# Sens_BMP085.net
KiCad netlist of a schematic drawn in EAGLE
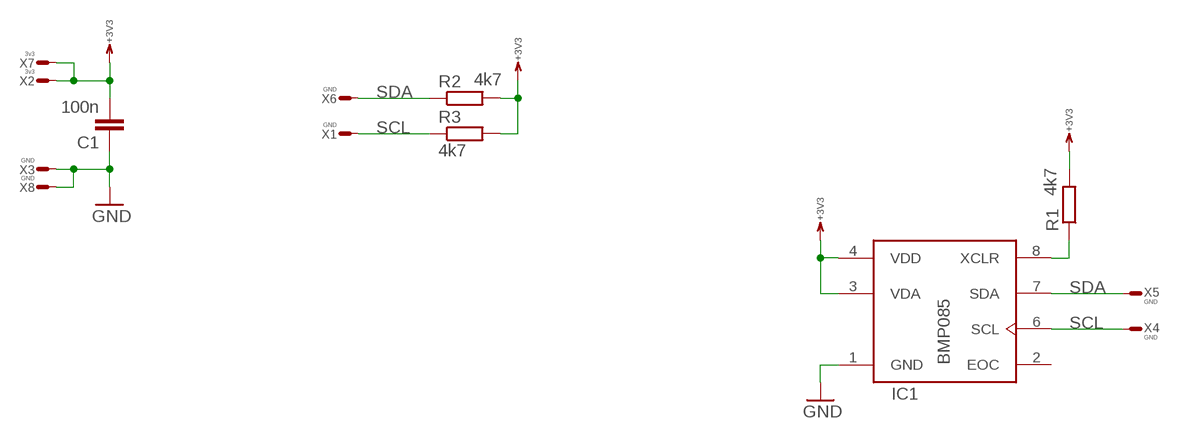
[diagram p0: schematic, sheet 1]

(export (version "E")
  (design (tool "Eeschema 10.0.6"))
  (components
    (comp (ref "C1")
      (value "100n")
      (footprint "eagle-import:0603")
      (libsource (lib "eagle-import") (part "C0603"))
    )
    (comp (ref "IC1")
      (value "BMP085")
      (footprint "eagle-import:LCC8")
      (libsource (lib "eagle-import") (part "BMP085"))
    )
    (comp (ref "R1")
      (value "4k7")
      (footprint "eagle-import:0603")
      (libsource (lib "eagle-import") (part "R0603"))
    )
    (comp (ref "R2")
      (value "4k7")
      (footprint "eagle-import:0603")
      (libsource (lib "eagle-import") (part "R0603"))
    )
    (comp (ref "R3")
      (value "4k7")
      (footprint "eagle-import:0603")
      (libsource (lib "eagle-import") (part "R0603"))
    )
    (comp (ref "X1")
      (value "GND")
      (footprint "eagle-import:T1.6_0.9")
      (libsource (lib "eagle-import") (part "WIREPADT1.6/0.9"))
    )
    (comp (ref "X2")
      (value "3v3")
      (footprint "eagle-import:T1.6_0.9")
      (libsource (lib "eagle-import") (part "WIREPADT1.6/0.9"))
    )
    (comp (ref "X3")
      (value "GND")
      (footprint "eagle-import:T1.6_0.9")
      (libsource (lib "eagle-import") (part "WIREPADT1.6/0.9"))
    )
    (comp (ref "X4")
      (value "GND")
      (footprint "eagle-import:T1.6_0.9")
      (libsource (lib "eagle-import") (part "WIREPADT1.6/0.9"))
    )
    (comp (ref "X5")
      (value "GND")
      (footprint "eagle-import:T1.6_0.9")
      (libsource (lib "eagle-import") (part "WIREPADT1.6/0.9"))
    )
    (comp (ref "X6")
      (value "GND")
      (footprint "eagle-import:T1.6_0.9")
      (libsource (lib "eagle-import") (part "WIREPADT1.6/0.9"))
    )
    (comp (ref "X7")
      (value "3v3")
      (footprint "eagle-import:T1.6_0.9")
      (libsource (lib "eagle-import") (part "WIREPADT1.6/0.9"))
    )
    (comp (ref "X8")
      (value "GND")
      (footprint "eagle-import:T1.6_0.9")
      (libsource (lib "eagle-import") (part "WIREPADT1.6/0.9"))
    )
  )
  (nets
    (net (code "1") (name "+3V3") (class "Default")
      (node (ref "C1") (pin "2") (pinfunction "2_2") (pintype "passive"))
      (node (ref "IC1") (pin "3") (pinfunction "VDA_3") (pintype "input"))
      (node (ref "IC1") (pin "4") (pinfunction "VDD_4") (pintype "input"))
      (node (ref "R1") (pin "2") (pinfunction "2_2") (pintype "passive"))
      (node (ref "R2") (pin "2") (pinfunction "2_2") (pintype "passive"))
      (node (ref "R3") (pin "2") (pinfunction "2_2") (pintype "passive"))
      (node (ref "X2") (pin "1") (pinfunction "S_1") (pintype "passive"))
      (node (ref "X7") (pin "1") (pinfunction "S_1") (pintype "passive"))
    )
    (net (code "2") (name "/SCL") (class "Default")
      (node (ref "IC1") (pin "6") (pinfunction "SCL_6") (pintype "input"))
      (node (ref "R3") (pin "1") (pinfunction "1_1") (pintype "passive"))
      (node (ref "X1") (pin "1") (pinfunction "S_1") (pintype "passive"))
      (node (ref "X4") (pin "1") (pinfunction "S_1") (pintype "passive"))
    )
    (net (code "3") (name "/SDA") (class "Default")
      (node (ref "IC1") (pin "7") (pinfunction "SDA_7") (pintype "bidirectional"))
      (node (ref "R2") (pin "1") (pinfunction "1_1") (pintype "passive"))
      (node (ref "X5") (pin "1") (pinfunction "S_1") (pintype "passive"))
      (node (ref "X6") (pin "1") (pinfunction "S_1") (pintype "passive"))
    )
    (net (code "4") (name "GND") (class "Default")
      (node (ref "C1") (pin "1") (pinfunction "1_1") (pintype "passive"))
      (node (ref "IC1") (pin "1") (pinfunction "GND_1") (pintype "input"))
      (node (ref "X3") (pin "1") (pinfunction "S_1") (pintype "passive"))
      (node (ref "X8") (pin "1") (pinfunction "S_1") (pintype "passive"))
    )
    (net (code "5") (name "Net-(IC1-XCLR)") (class "Default")
      (node (ref "IC1") (pin "8") (pinfunction "XCLR_8") (pintype "input"))
      (node (ref "R1") (pin "1") (pinfunction "1_1") (pintype "passive"))
    )
    (net (code "6") (name "unconnected-(IC1-EOC-Pad2)") (class "Default")
      (node (ref "IC1") (pin "2") (pinfunction "EOC_2") (pintype "output"))
    )
  )
)
